# sensore_temp.net
KiCad netlist of a schematic drawn in EAGLE
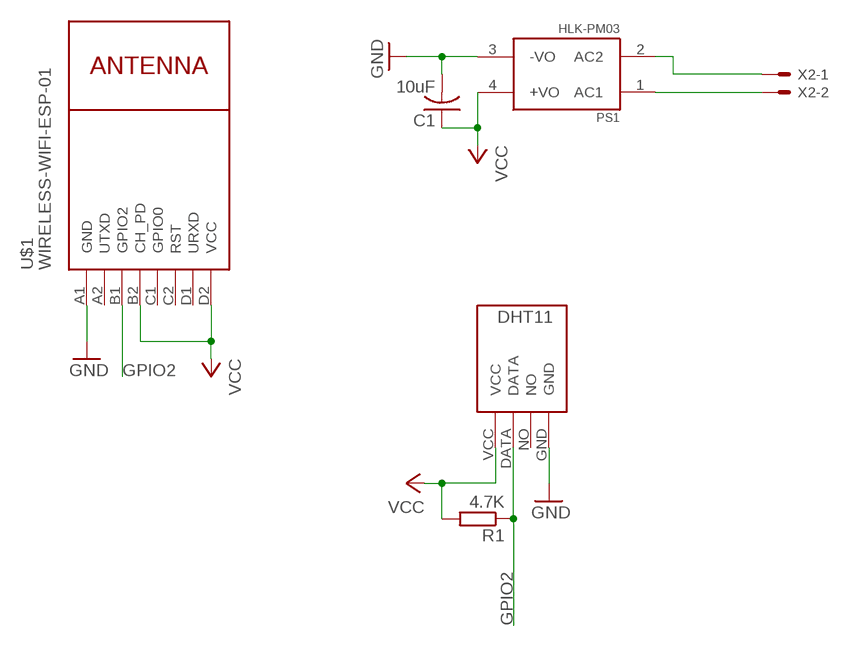
[diagram p0: schematic, sheet 1]

(export (version "E")
  (design (tool "Eeschema 10.0.6"))
  (components
    (comp (ref "C1")
      (value "10uF")
      (footprint "eagle-import:C025-025X050")
      (libsource (lib "eagle-import") (part "C-US025-025X050"))
    )
    (comp (ref "PS1")
      (value "HLK-PM03")
      (footprint "eagle-import:CONV_HLK-PM03")
      (fields (field (name "MF") "Hi-link"))
      (libsource (lib "eagle-import") (part "HLK-PM03"))
    )
    (comp (ref "R1")
      (value "4.7K")
      (footprint "eagle-import:0204_7")
      (libsource (lib "eagle-import") (part "R-EU_0204/7"))
    )
    (comp (ref "U$1")
      (value "WIRELESS-WIFI-ESP-01")
      (footprint "eagle-import:WIRELESS-WIFI-ESP-01")
      (libsource (lib "eagle-import") (part "WIRELESS-WIFI-ESP-01"))
    )
    (comp (ref "U$2")
      (value "DHT11")
      (footprint "eagle-import:DHT11")
      (libsource (lib "eagle-import") (part "DHT11"))
    )
    (comp (ref "X2")
      (value "JST-XH-02-PIN-LONG-PAD")
      (footprint "eagle-import:JST-XH-02-PACKAGE-LONG-PAD")
      (libsource (lib "eagle-import") (part "JST-XH-02-PIN-LONG-PAD"))
    )
  )
  (nets
    (net (code "1") (name "/GPIO2") (class "Default")
      (node (ref "R1") (pin "1") (pinfunction "1_1") (pintype "passive"))
      (node (ref "U$1") (pin "B1") (pinfunction "GPIO2_B1") (pintype "bidirectional"))
      (node (ref "U$2") (pin "DATA") (pinfunction "DATA_DATA") (pintype "bidirectional"))
    )
    (net (code "2") (name "GND") (class "Default")
      (node (ref "C1") (pin "2") (pinfunction "2_2") (pintype "passive"))
      (node (ref "PS1") (pin "3") (pinfunction "-VO_3") (pintype "output"))
      (node (ref "U$1") (pin "A1") (pinfunction "GND_A1") (pintype "power_in"))
      (node (ref "U$2") (pin "GND") (pinfunction "GND_GND") (pintype "bidirectional"))
    )
    (net (code "3") (name "Net-(PS1-AC1)") (class "Default")
      (node (ref "PS1") (pin "1") (pinfunction "AC1_1") (pintype "input"))
      (node (ref "X2") (pin "2") (pinfunction "S_2") (pintype "passive"))
    )
    (net (code "4") (name "Net-(PS1-AC2)") (class "Default")
      (node (ref "PS1") (pin "2") (pinfunction "AC2_2") (pintype "input"))
      (node (ref "X2") (pin "1") (pinfunction "S_1") (pintype "passive"))
    )
    (net (code "5") (name "VCC") (class "Default")
      (node (ref "C1") (pin "1") (pinfunction "1_1") (pintype "passive"))
      (node (ref "PS1") (pin "4") (pinfunction "+VO_4") (pintype "output"))
      (node (ref "R1") (pin "2") (pinfunction "2_2") (pintype "passive"))
      (node (ref "U$1") (pin "B2") (pinfunction "CH_PD_B2") (pintype "bidirectional"))
      (node (ref "U$1") (pin "D2") (pinfunction "VCC_D2") (pintype "power_in"))
      (node (ref "U$2") (pin "VCC") (pinfunction "VCC_VCC") (pintype "bidirectional"))
    )
    (net (code "6") (name "unconnected-(U$1-GPIO0-PadC1)") (class "Default")
      (node (ref "U$1") (pin "C1") (pinfunction "GPIO0_C1") (pintype "bidirectional"))
    )
    (net (code "7") (name "unconnected-(U$1-RST-PadC2)") (class "Default")
      (node (ref "U$1") (pin "C2") (pinfunction "RST_C2") (pintype "bidirectional"))
    )
    (net (code "8") (name "unconnected-(U$1-URXD-PadD1)") (class "Default")
      (node (ref "U$1") (pin "D1") (pinfunction "URXD_D1") (pintype "bidirectional"))
    )
    (net (code "9") (name "unconnected-(U$1-UTXD-PadA2)") (class "Default")
      (node (ref "U$1") (pin "A2") (pinfunction "UTXD_A2") (pintype "bidirectional"))
    )
    (net (code "10") (name "unconnected-(U$2-PadNO)") (class "Default")
      (node (ref "U$2") (pin "NO") (pinfunction "NO_NO") (pintype "bidirectional"))
    )
  )
)
